# CH32V467RET-R0.net
KiCad netlist of a schematic drawn in Altium Designer
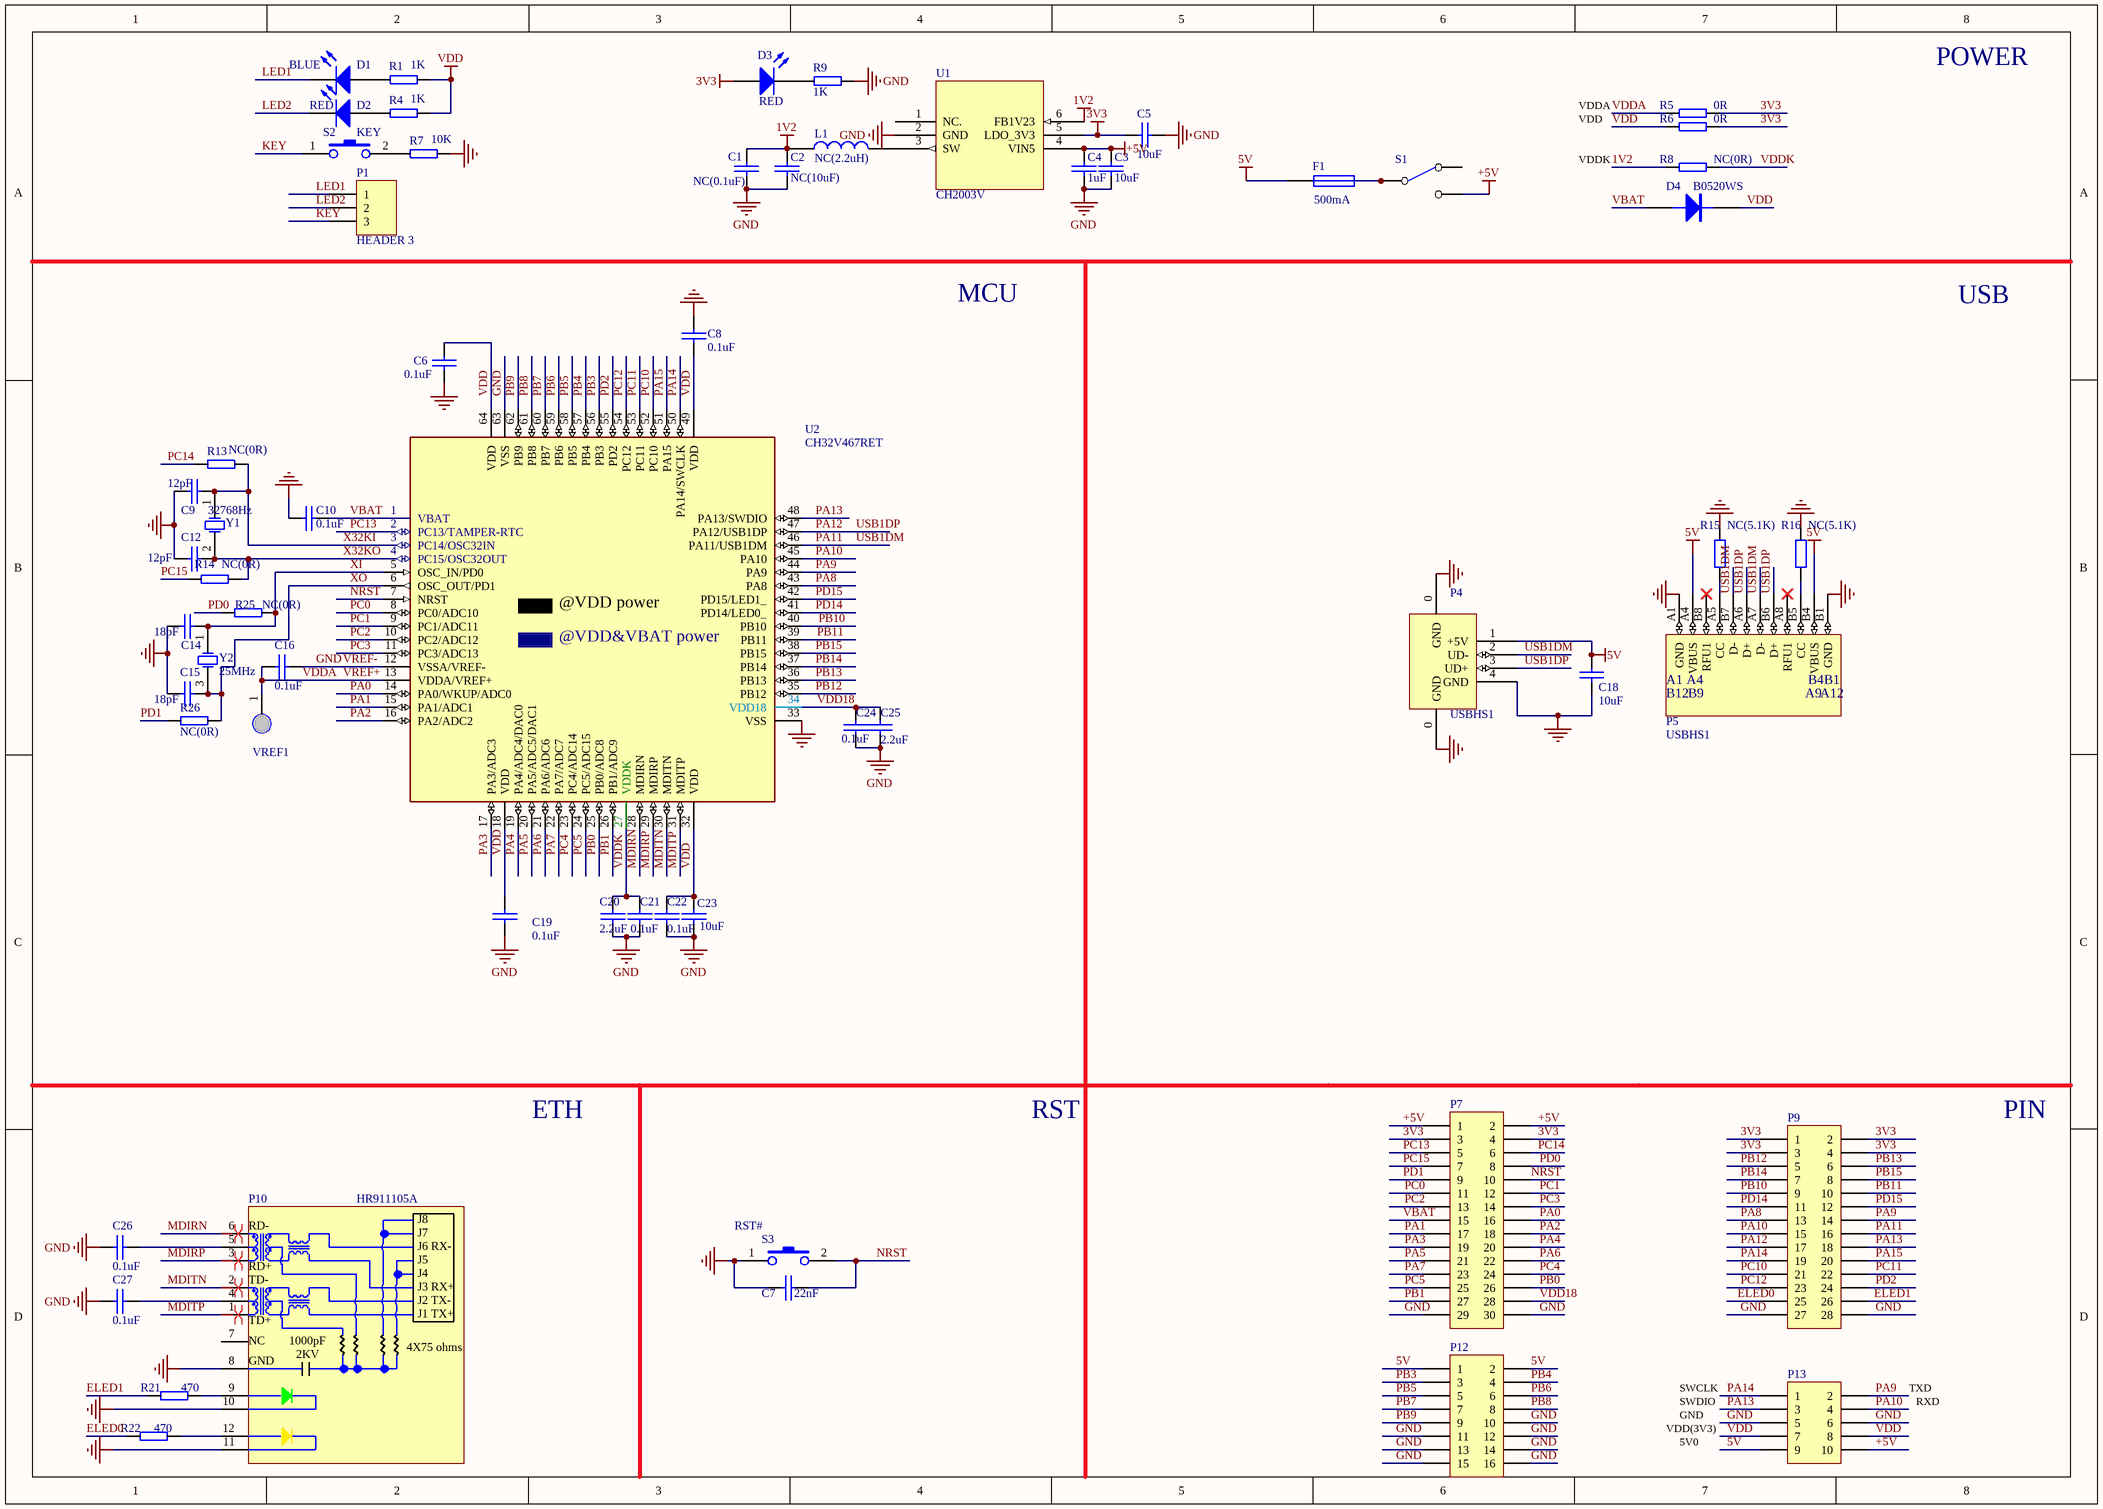
[diagram p0: CH32V467RET-R0.SchDoc]

(export (version "E")
  (design (tool "Eeschema 10.0.6"))
  (components
    (comp (ref "C1")
      (value "NC(0.1uF)")
      (footprint "0402_C")
      (description "Capacitor")
      (libsource (lib "") (part "CAP_2"))
    )
    (comp (ref "C2")
      (value "NC(10uF)")
      (footprint "0603_C")
      (description "Capacitor")
      (libsource (lib "*") (part "CAP"))
    )
    (comp (ref "C3")
      (value "10uF")
      (footprint "0603_C")
      (description "Capacitor")
      (libsource (lib "*") (part "CAP"))
    )
    (comp (ref "C4")
      (value "1uF")
      (footprint "0402_C")
      (description "Capacitor")
      (libsource (lib "") (part "CAP_2"))
    )
    (comp (ref "C5")
      (value "10uF")
      (footprint "0603_C")
      (description "Capacitor")
      (libsource (lib "*") (part "CAP"))
    )
    (comp (ref "C6")
      (value "0.1uF")
      (footprint "0402_C")
      (description "Capacitor")
      (libsource (lib "*") (part "CAP"))
    )
    (comp (ref "C7")
      (value "22nF")
      (footprint "0402_C")
      (description "Capacitor")
      (libsource (lib "") (part "CAP_1"))
    )
    (comp (ref "C8")
      (value "0.1uF")
      (footprint "0402_C")
      (description "Capacitor")
      (libsource (lib "*") (part "CAP"))
    )
    (comp (ref "C9")
      (value "12pF")
      (footprint "0402_C")
      (description "Capacitor")
      (libsource (lib "*") (part "CAP"))
    )
    (comp (ref "C10")
      (value "0.1uF")
      (footprint "0402_C")
      (description "Capacitor")
      (libsource (lib "*") (part "CAP"))
    )
    (comp (ref "C12")
      (value "12pF")
      (footprint "0402_C")
      (description "Capacitor")
      (libsource (lib "*") (part "CAP"))
    )
    (comp (ref "C14")
      (value "18pF")
      (footprint "0402_C")
      (description "Capacitor")
      (libsource (lib "*") (part "CAP"))
    )
    (comp (ref "C15")
      (value "18pF")
      (footprint "0402_C")
      (description "Capacitor")
      (libsource (lib "*") (part "CAP"))
    )
    (comp (ref "C16")
      (value "0.1uF")
      (footprint "0402_C")
      (description "Capacitor")
      (libsource (lib "*") (part "CAP"))
    )
    (comp (ref "C18")
      (value "10uF")
      (footprint "0603_C")
      (description "Capacitor")
      (libsource (lib "") (part "CAP_1"))
    )
    (comp (ref "C19")
      (value "0.1uF")
      (footprint "0402_C")
      (description "Capacitor")
      (libsource (lib "*") (part "CAP"))
    )
    (comp (ref "C20")
      (value "2.2uF")
      (footprint "0402_C")
      (description "Capacitor")
      (libsource (lib "*") (part "CAP"))
    )
    (comp (ref "C21")
      (value "0.1uF")
      (footprint "0402_C")
      (description "Capacitor")
      (libsource (lib "*") (part "CAP"))
    )
    (comp (ref "C22")
      (value "0.1uF")
      (footprint "0402_C")
      (description "Capacitor")
      (libsource (lib "*") (part "CAP"))
    )
    (comp (ref "C23")
      (value "10uF")
      (footprint "0603_C")
      (description "Capacitor")
      (libsource (lib "wch_sch_others") (part "CAP"))
    )
    (comp (ref "C24")
      (value "0.1uF")
      (footprint "0402_C")
      (description "Capacitor")
      (libsource (lib "*") (part "CAP"))
    )
    (comp (ref "C25")
      (value "2.2uF")
      (footprint "0402_C")
      (description "Capacitor")
      (libsource (lib "*") (part "CAP"))
    )
    (comp (ref "C26")
      (value "0.1uF")
      (footprint "0402_C")
      (description "Capacitor")
      (libsource (lib "wch_sch_others") (part "CAP"))
    )
    (comp (ref "C27")
      (value "0.1uF")
      (footprint "0402_C")
      (description "Capacitor")
      (libsource (lib "wch_sch_others") (part "CAP"))
    )
    (comp (ref "D1")
      (value "BLUE")
      (footprint "0603+")
      (description "Typical INFRARED GaAs LED")
      (fields (field (name "PUBLISHER") "Altium Limited"))
      (libsource (lib "*") (part "LED0"))
    )
    (comp (ref "D2")
      (value "RED")
      (footprint "0603+")
      (description "Typical INFRARED GaAs LED")
      (fields (field (name "PUBLISHER") "Altium Limited"))
      (libsource (lib "*") (part "LED0"))
    )
    (comp (ref "D3")
      (value "RED")
      (footprint "0603+")
      (description "Typical INFRARED GaAs LED")
      (fields (field (name "PUBLISHER") "Altium Limited"))
      (libsource (lib "*") (part "LED0"))
    )
    (comp (ref "D4")
      (value "B0520WS")
      (footprint "SOD-323")
      (description "Diode")
      (libsource (lib "*") (part "DIODE"))
    )
    (comp (ref "F1")
      (value "500mA")
      (footprint "0603")
      (description "Fuse")
      (libsource (lib "wch_sch_others") (part "FUSE1"))
    )
    (comp (ref "L1") (value "NC(2.2uH)") (footprint "CD32") (libsource (lib "*") (part "INDUCTOR")))
    (comp (ref "P1")
      (value "HEADER 3")
      (footprint "SIP3-2.54MM")
      (description "Header, 3-Pin")
      (libsource (lib "wch_sch_others") (part "HEADER 3"))
    )
    (comp (ref "P4")
      (value "USBHS1")
      (footprint "USBAF")
      (description "USB Port")
      (libsource (lib "*") (part "USB"))
    )
    (comp (ref "P5")
      (value "USBHS1")
      (footprint "TYPE-C-Receptacle-2.0")
      (libsource (lib "*") (part "TYPE-C1"))
    )
    (comp (ref "P7")
      (value "HEADER 15x2")
      (footprint "MYPCB:IDC30-2.54MM")
      (description "Header, 15-Pin, Dual row")
      (libsource (lib "wch_sch_others") (part "HEADER 15x2"))
    )
    (comp (ref "P9")
      (value "HEADER 14x2")
      (footprint "MYPCB:IDC28-2.54MM")
      (description "Header, 14-Pin, Dual row")
      (libsource (lib "wch_sch_others") (part "HEADER 14x2"))
    )
    (comp (ref "P10") (value "HR911105A") (footprint "HR911105A") (libsource (lib "*") (part "HR911105A")))
    (comp (ref "P12")
      (value "Ppin")
      (footprint "IDC16-2.54mm")
      (description "Header, 8-Pin, Dual row, Right Angle")
      (fields (field (name "PUBLISHER") "Altium Limited"))
      (libsource (lib "Miscellaneous Connectors") (part "Header 8X2H"))
    )
    (comp (ref "P13")
      (value "LINK")
      (footprint "IDC10-2.54mm")
      (description "Header, 5-Pin, Dual row, Right Angle")
      (fields (field (name "PUBLISHER") "Altium Limited"))
      (libsource (lib "Miscellaneous Connectors") (part "Header 5X2H"))
    )
    (comp (ref "R1") (value "1K") (footprint "0402") (libsource (lib "wch_sch_others") (part "RES")))
    (comp (ref "R4") (value "1K") (footprint "0402") (libsource (lib "wch_sch_others") (part "RES")))
    (comp (ref "R5") (value "0R") (footprint "0402") (libsource (lib "*") (part "R")))
    (comp (ref "R6") (value "0R") (footprint "0402") (libsource (lib "*") (part "R")))
    (comp (ref "R7") (value "10K") (footprint "0402") (libsource (lib "wch_sch_others") (part "RES")))
    (comp (ref "R8") (value "NC(0R)") (footprint "0402") (libsource (lib "*") (part "R")))
    (comp (ref "R9") (value "1K") (footprint "0402") (libsource (lib "wch_sch_others") (part "RES")))
    (comp (ref "R13") (value "NC(0R)") (footprint "0402") (libsource (lib "wch_sch_others") (part "RES")))
    (comp (ref "R14") (value "NC(0R)") (footprint "0402") (libsource (lib "wch_sch_others") (part "RES")))
    (comp (ref "R15")
      (value "NC(5.1K)")
      (footprint "0402")
      (description "Resistor")
      (libsource (lib "Miscellaneous Devices") (part "Res2"))
    )
    (comp (ref "R16")
      (value "NC(5.1K)")
      (footprint "0402")
      (description "Resistor")
      (libsource (lib "Miscellaneous Devices") (part "Res2"))
    )
    (comp (ref "R21") (value "470") (footprint "0402") (libsource (lib "wch_sch_others") (part "RES")))
    (comp (ref "R22") (value "470") (footprint "0402") (libsource (lib "wch_sch_others") (part "RES")))
    (comp (ref "R25") (value "NC(0R)") (footprint "0402") (libsource (lib "wch_sch_others") (part "RES")))
    (comp (ref "R26") (value "NC(0R)") (footprint "0402") (libsource (lib "wch_sch_others") (part "RES")))
    (comp (ref "S1") (value "SW SPDT") (footprint "SW1") (libsource (lib "*") (part "SW SPDT")))
    (comp (ref "S2")
      (value "KEY")
      (footprint "SMD_6.1x3.65x2.5mm-KEY")
      (libsource (lib "wch_sch_others") (part "KEY1"))
    )
    (comp (ref "S3")
      (value "RST#")
      (footprint "SMD_6.1x3.65x2.5mm-KEY")
      (libsource (lib "wch_sch_others") (part "KEY1"))
    )
    (comp (ref "U1")
      (value "CH2003V")
      (footprint "SOT-23-6")
      (description "Step-Down DC-DC Converter, 5V input, 1.23V * 800mA output, with LDO 3.3V * 200mA")
      (libsource (lib "CHXXX") (part "CH2003V"))
    )
    (comp (ref "U2")
      (value "CH32V467RET")
      (footprint "LQFP64_7X7")
      (description "RISC-V FPU HD-MCU, 175MHz, USB_480M, 100M Ethernet & Phy, CAN, ADC, DAC, SRAM")
      (libsource (lib "CHXXX") (part "CH32V467RET"))
    )
    (comp (ref "VREF1")
      (value "PAD")
      (footprint "TESTPOINT1")
      (description "焊盘")
      (libsource (lib "wch_sch_others") (part "PAD"))
    )
    (comp (ref "Y1")
      (value "32768Hz")
      (footprint "FC-135")
      (description "Crystal Oscillator")
      (fields (field (name "PUBLISHER") "Altium Limited"))
      (libsource (lib "*") (part "XTAL"))
    )
    (comp (ref "Y2")
      (value "25MHz")
      (footprint "XT3225")
      (description "Crystal Oscillator")
      (fields (field (name "PUBLISHER") "Altium Limited"))
      (libsource (lib "") (part "XTAL_1"))
    )
  )
  (nets
    (net (code "1") (name "+5V") (class "Default")
      (node (ref "C3") (pin "2") (pinfunction "2_2") (pintype "passive"))
      (node (ref "C4") (pin "2") (pinfunction "2_2") (pintype "passive"))
      (node (ref "P13") (pin "10") (pinfunction "10_10") (pintype "passive"))
      (node (ref "P7") (pin "1") (pinfunction "1_1") (pintype "passive"))
      (node (ref "P7") (pin "2") (pinfunction "2_2") (pintype "passive"))
      (node (ref "S1") (pin "2") (pinfunction "NC_2") (pintype "passive"))
      (node (ref "U1") (pin "4") (pinfunction "VIN5_4") (pintype "power_in"))
    )
    (net (code "3") (name "/ELED0") (class "Default")
      (node (ref "P9") (pin "25") (pinfunction "25_25") (pintype "passive"))
      (node (ref "R22") (pin "1") (pintype "passive"))
    )
    (net (code "4") (name "/ELED1") (class "Default")
      (node (ref "P9") (pin "26") (pinfunction "26_26") (pintype "passive"))
      (node (ref "R21") (pin "1") (pintype "passive"))
    )
    (net (code "5") (name "/KEY") (class "Default")
      (node (ref "P1") (pin "3") (pinfunction "3_3") (pintype "passive"))
      (node (ref "S2") (pin "1") (pinfunction "1_1") (pintype "passive"))
    )
    (net (code "6") (name "/LED1") (class "Default")
      (node (ref "D1") (pin "2") (pinfunction "K_2") (pintype "passive"))
      (node (ref "P1") (pin "1") (pinfunction "1_1") (pintype "passive"))
    )
    (net (code "7") (name "/LED2") (class "Default")
      (node (ref "D2") (pin "2") (pinfunction "K_2") (pintype "passive"))
      (node (ref "P1") (pin "2") (pinfunction "2_2") (pintype "passive"))
    )
    (net (code "8") (name "/MDIRN") (class "Default")
      (node (ref "P10") (pin "6") (pintype "passive"))
      (node (ref "U2") (pin "28") (pinfunction "MDIRN_28") (pintype "bidirectional"))
    )
    (net (code "9") (name "/MDIRP") (class "Default")
      (node (ref "P10") (pin "3") (pintype "passive"))
      (node (ref "U2") (pin "29") (pinfunction "MDIRP_29") (pintype "bidirectional"))
    )
    (net (code "10") (name "/MDITN") (class "Default")
      (node (ref "P10") (pin "2") (pintype "passive"))
      (node (ref "U2") (pin "30") (pinfunction "MDITN_30") (pintype "bidirectional"))
    )
    (net (code "11") (name "/MDITP") (class "Default")
      (node (ref "P10") (pin "1") (pintype "passive"))
      (node (ref "U2") (pin "31") (pinfunction "MDITP_31") (pintype "bidirectional"))
    )
    (net (code "12") (name "/NRST") (class "Default")
      (node (ref "C7") (pin "2") (pinfunction "2_2") (pintype "passive"))
      (node (ref "P7") (pin "10") (pinfunction "10_10") (pintype "passive"))
      (node (ref "S3") (pin "2") (pinfunction "2_2") (pintype "passive"))
      (node (ref "U2") (pin "7") (pinfunction "NRST_7") (pintype "input"))
    )
    (net (code "13") (name "/PA0") (class "Default")
      (node (ref "P7") (pin "16") (pinfunction "16_16") (pintype "passive"))
      (node (ref "U2") (pin "14") (pinfunction "PA0/WKUP/ADC0_14") (pintype "bidirectional"))
    )
    (net (code "14") (name "/PA1") (class "Default")
      (node (ref "P7") (pin "17") (pinfunction "17_17") (pintype "passive"))
      (node (ref "U2") (pin "15") (pinfunction "PA1/ADC1_15") (pintype "bidirectional"))
    )
    (net (code "15") (name "/PA2") (class "Default")
      (node (ref "P7") (pin "18") (pinfunction "18_18") (pintype "passive"))
      (node (ref "U2") (pin "16") (pinfunction "PA2/ADC2_16") (pintype "bidirectional"))
    )
    (net (code "16") (name "/PA3") (class "Default")
      (node (ref "P7") (pin "19") (pinfunction "19_19") (pintype "passive"))
      (node (ref "U2") (pin "17") (pinfunction "PA3/ADC3_17") (pintype "bidirectional"))
    )
    (net (code "17") (name "/PA4") (class "Default")
      (node (ref "P7") (pin "20") (pinfunction "20_20") (pintype "passive"))
      (node (ref "U2") (pin "19") (pinfunction "PA4/ADC4/DAC0_19") (pintype "bidirectional"))
    )
    (net (code "18") (name "/PA5") (class "Default")
      (node (ref "P7") (pin "21") (pinfunction "21_21") (pintype "passive"))
      (node (ref "U2") (pin "20") (pinfunction "PA5/ADC5/DAC1_20") (pintype "bidirectional"))
    )
    (net (code "19") (name "/PA6") (class "Default")
      (node (ref "P7") (pin "22") (pinfunction "22_22") (pintype "passive"))
      (node (ref "U2") (pin "21") (pinfunction "PA6/ADC6_21") (pintype "bidirectional"))
    )
    (net (code "20") (name "/PA7") (class "Default")
      (node (ref "P7") (pin "23") (pinfunction "23_23") (pintype "passive"))
      (node (ref "U2") (pin "22") (pinfunction "PA7/ADC7_22") (pintype "bidirectional"))
    )
    (net (code "21") (name "/PA8") (class "Default")
      (node (ref "P9") (pin "13") (pinfunction "13_13") (pintype "passive"))
      (node (ref "U2") (pin "43") (pinfunction "PA8_43") (pintype "bidirectional"))
    )
    (net (code "22") (name "/PA9") (class "Default")
      (node (ref "P13") (pin "2") (pinfunction "2_2") (pintype "passive"))
      (node (ref "P9") (pin "14") (pinfunction "14_14") (pintype "passive"))
      (node (ref "U2") (pin "44") (pinfunction "PA9_44") (pintype "bidirectional"))
    )
    (net (code "23") (name "/PA10") (class "Default")
      (node (ref "P13") (pin "4") (pinfunction "4_4") (pintype "passive"))
      (node (ref "P9") (pin "15") (pinfunction "15_15") (pintype "passive"))
      (node (ref "U2") (pin "45") (pinfunction "PA10_45") (pintype "bidirectional"))
    )
    (net (code "24") (name "/PA11") (class "Default")
      (node (ref "P4") (pin "2") (pinfunction "UD-_2") (pintype "bidirectional"))
      (node (ref "P5") (pin "A7") (pinfunction "D-_A7") (pintype "bidirectional"))
      (node (ref "P5") (pin "B7") (pinfunction "D-_B7") (pintype "bidirectional"))
      (node (ref "P9") (pin "16") (pinfunction "16_16") (pintype "passive"))
      (node (ref "U2") (pin "46") (pinfunction "PA11/USB1DM_46") (pintype "bidirectional"))
    )
    (net (code "25") (name "/PA12") (class "Default")
      (node (ref "P4") (pin "3") (pinfunction "UD+_3") (pintype "bidirectional"))
      (node (ref "P5") (pin "A6") (pinfunction "D+_A6") (pintype "bidirectional"))
      (node (ref "P5") (pin "B6") (pinfunction "D+_B6") (pintype "bidirectional"))
      (node (ref "P9") (pin "17") (pinfunction "17_17") (pintype "passive"))
      (node (ref "U2") (pin "47") (pinfunction "PA12/USB1DP_47") (pintype "bidirectional"))
    )
    (net (code "26") (name "/PA13") (class "Default")
      (node (ref "P13") (pin "3") (pinfunction "3_3") (pintype "passive"))
      (node (ref "P9") (pin "18") (pinfunction "18_18") (pintype "passive"))
      (node (ref "U2") (pin "48") (pinfunction "PA13/SWDIO_48") (pintype "bidirectional"))
    )
    (net (code "27") (name "/PA14") (class "Default")
      (node (ref "P13") (pin "1") (pinfunction "1_1") (pintype "passive"))
      (node (ref "P9") (pin "19") (pinfunction "19_19") (pintype "passive"))
      (node (ref "U2") (pin "50") (pinfunction "PA14/SWCLK_50") (pintype "bidirectional"))
    )
    (net (code "28") (name "/PA15") (class "Default")
      (node (ref "P9") (pin "20") (pinfunction "20_20") (pintype "passive"))
      (node (ref "U2") (pin "51") (pinfunction "PA15_51") (pintype "bidirectional"))
    )
    (net (code "29") (name "/PB0") (class "Default")
      (node (ref "P7") (pin "26") (pinfunction "26_26") (pintype "passive"))
      (node (ref "U2") (pin "25") (pinfunction "PB0/ADC8_25") (pintype "bidirectional"))
    )
    (net (code "30") (name "/PB1") (class "Default")
      (node (ref "P7") (pin "27") (pinfunction "27_27") (pintype "passive"))
      (node (ref "U2") (pin "26") (pinfunction "PB1/ADC9_26") (pintype "bidirectional"))
    )
    (net (code "31") (name "/PB3") (class "Default")
      (node (ref "P12") (pin "3") (pinfunction "3_3") (pintype "passive"))
      (node (ref "U2") (pin "56") (pinfunction "PB3_56") (pintype "bidirectional"))
    )
    (net (code "32") (name "/PB4") (class "Default")
      (node (ref "P12") (pin "4") (pinfunction "4_4") (pintype "passive"))
      (node (ref "U2") (pin "57") (pinfunction "PB4_57") (pintype "bidirectional"))
    )
    (net (code "33") (name "/PB5") (class "Default")
      (node (ref "P12") (pin "5") (pinfunction "5_5") (pintype "passive"))
      (node (ref "U2") (pin "58") (pinfunction "PB5_58") (pintype "bidirectional"))
    )
    (net (code "34") (name "/PB6") (class "Default")
      (node (ref "P12") (pin "6") (pinfunction "6_6") (pintype "passive"))
      (node (ref "U2") (pin "59") (pinfunction "PB6_59") (pintype "bidirectional"))
    )
    (net (code "35") (name "/PB7") (class "Default")
      (node (ref "P12") (pin "7") (pinfunction "7_7") (pintype "passive"))
      (node (ref "U2") (pin "60") (pinfunction "PB7_60") (pintype "bidirectional"))
    )
    (net (code "36") (name "/PB8") (class "Default")
      (node (ref "P12") (pin "8") (pinfunction "8_8") (pintype "passive"))
      (node (ref "U2") (pin "61") (pinfunction "PB8_61") (pintype "bidirectional"))
    )
    (net (code "37") (name "/PB9") (class "Default")
      (node (ref "P12") (pin "9") (pinfunction "9_9") (pintype "passive"))
      (node (ref "U2") (pin "62") (pinfunction "PB9_62") (pintype "bidirectional"))
    )
    (net (code "38") (name "/PB10") (class "Default")
      (node (ref "P9") (pin "9") (pinfunction "9_9") (pintype "passive"))
      (node (ref "U2") (pin "40") (pinfunction "PB10_40") (pintype "bidirectional"))
    )
    (net (code "39") (name "/PB11") (class "Default")
      (node (ref "P9") (pin "10") (pinfunction "10_10") (pintype "passive"))
      (node (ref "U2") (pin "39") (pinfunction "PB11_39") (pintype "bidirectional"))
    )
    (net (code "40") (name "/PB12") (class "Default")
      (node (ref "P9") (pin "5") (pinfunction "5_5") (pintype "passive"))
      (node (ref "U2") (pin "35") (pinfunction "PB12_35") (pintype "bidirectional"))
    )
    (net (code "41") (name "/PB13") (class "Default")
      (node (ref "P9") (pin "6") (pinfunction "6_6") (pintype "passive"))
      (node (ref "U2") (pin "36") (pinfunction "PB13_36") (pintype "bidirectional"))
    )
    (net (code "42") (name "/PB14") (class "Default")
      (node (ref "P9") (pin "7") (pinfunction "7_7") (pintype "passive"))
      (node (ref "U2") (pin "37") (pinfunction "PB14_37") (pintype "bidirectional"))
    )
    (net (code "43") (name "/PB15") (class "Default")
      (node (ref "P9") (pin "8") (pinfunction "8_8") (pintype "passive"))
      (node (ref "U2") (pin "38") (pinfunction "PB15_38") (pintype "bidirectional"))
    )
    (net (code "44") (name "/PC0") (class "Default")
      (node (ref "P7") (pin "11") (pinfunction "11_11") (pintype "passive"))
      (node (ref "U2") (pin "8") (pinfunction "PC0/ADC10_8") (pintype "bidirectional"))
    )
    (net (code "45") (name "/PC1") (class "Default")
      (node (ref "P7") (pin "12") (pinfunction "12_12") (pintype "passive"))
      (node (ref "U2") (pin "9") (pinfunction "PC1/ADC11_9") (pintype "bidirectional"))
    )
    (net (code "46") (name "/PC2") (class "Default")
      (node (ref "P7") (pin "13") (pinfunction "13_13") (pintype "passive"))
      (node (ref "U2") (pin "10") (pinfunction "PC2/ADC12_10") (pintype "bidirectional"))
    )
    (net (code "47") (name "/PC3") (class "Default")
      (node (ref "P7") (pin "14") (pinfunction "14_14") (pintype "passive"))
      (node (ref "U2") (pin "11") (pinfunction "PC3/ADC13_11") (pintype "bidirectional"))
    )
    (net (code "48") (name "/PC4") (class "Default")
      (node (ref "P7") (pin "24") (pinfunction "24_24") (pintype "passive"))
      (node (ref "U2") (pin "23") (pinfunction "PC4/ADC14_23") (pintype "bidirectional"))
    )
    (net (code "49") (name "/PC5") (class "Default")
      (node (ref "P7") (pin "25") (pinfunction "25_25") (pintype "passive"))
      (node (ref "U2") (pin "24") (pinfunction "PC5/ADC15_24") (pintype "bidirectional"))
    )
    (net (code "50") (name "/PC10") (class "Default")
      (node (ref "P9") (pin "21") (pinfunction "21_21") (pintype "passive"))
      (node (ref "U2") (pin "52") (pinfunction "PC10_52") (pintype "bidirectional"))
    )
    (net (code "51") (name "/PC11") (class "Default")
      (node (ref "P9") (pin "22") (pinfunction "22_22") (pintype "passive"))
      (node (ref "U2") (pin "53") (pinfunction "PC11_53") (pintype "bidirectional"))
    )
    (net (code "52") (name "/PC12") (class "Default")
      (node (ref "P9") (pin "23") (pinfunction "23_23") (pintype "passive"))
      (node (ref "U2") (pin "54") (pinfunction "PC12_54") (pintype "bidirectional"))
    )
    (net (code "53") (name "/PC13") (class "Default")
      (node (ref "P7") (pin "5") (pinfunction "5_5") (pintype "passive"))
      (node (ref "U2") (pin "2") (pinfunction "PC13/TAMPER-RTC_2") (pintype "bidirectional"))
    )
    (net (code "54") (name "/PC14") (class "Default")
      (node (ref "P7") (pin "6") (pinfunction "6_6") (pintype "passive"))
      (node (ref "R13") (pin "1") (pintype "passive"))
    )
    (net (code "55") (name "/PC15") (class "Default")
      (node (ref "P7") (pin "7") (pinfunction "7_7") (pintype "passive"))
      (node (ref "R14") (pin "1") (pintype "passive"))
    )
    (net (code "56") (name "/PD0") (class "Default")
      (node (ref "P7") (pin "8") (pinfunction "8_8") (pintype "passive"))
      (node (ref "R25") (pin "1") (pintype "passive"))
    )
    (net (code "57") (name "/PD1") (class "Default")
      (node (ref "P7") (pin "9") (pinfunction "9_9") (pintype "passive"))
      (node (ref "R26") (pin "2") (pintype "passive"))
    )
    (net (code "58") (name "/PD2") (class "Default")
      (node (ref "P9") (pin "24") (pinfunction "24_24") (pintype "passive"))
      (node (ref "U2") (pin "55") (pinfunction "PD2_55") (pintype "bidirectional"))
    )
    (net (code "59") (name "/PD14") (class "Default")
      (node (ref "P9") (pin "11") (pinfunction "11_11") (pintype "passive"))
      (node (ref "U2") (pin "41") (pinfunction "PD14/LED0__41") (pintype "bidirectional"))
    )
    (net (code "60") (name "/PD15") (class "Default")
      (node (ref "P9") (pin "12") (pinfunction "12_12") (pintype "passive"))
      (node (ref "U2") (pin "42") (pinfunction "PD15/LED1__42") (pintype "bidirectional"))
    )
    (net (code "61") (name "/VBAT") (class "Default")
      (node (ref "C10") (pin "2") (pinfunction "2_2") (pintype "passive"))
      (node (ref "D4") (pin "1") (pinfunction "A_1") (pintype "passive"))
      (node (ref "P7") (pin "15") (pinfunction "15_15") (pintype "passive"))
      (node (ref "U2") (pin "1") (pinfunction "VBAT_1") (pintype "power_in"))
    )
    (net (code "62") (name "/VDD18") (class "Default")
      (node (ref "C24") (pin "2") (pinfunction "2_2") (pintype "passive"))
      (node (ref "C25") (pin "2") (pinfunction "2_2") (pintype "passive"))
      (node (ref "P7") (pin "28") (pinfunction "28_28") (pintype "passive"))
      (node (ref "U2") (pin "34") (pinfunction "VDD18_34") (pintype "power_in"))
    )
    (net (code "63") (name "/VDDA") (class "Default")
      (node (ref "C16") (pin "1") (pinfunction "1_1") (pintype "passive"))
      (node (ref "R5") (pin "2") (pinfunction "2_2") (pintype "passive"))
      (node (ref "U2") (pin "13") (pinfunction "VDDA/VREF+_13") (pintype "power_in"))
      (node (ref "VREF1") (pin "1") (pintype "passive"))
    )
    (net (code "64") (name "/VDDK") (class "Default")
      (node (ref "C20") (pin "2") (pinfunction "2_2") (pintype "passive"))
      (node (ref "C21") (pin "2") (pinfunction "2_2") (pintype "passive"))
      (node (ref "R8") (pin "1") (pinfunction "1_1") (pintype "passive"))
      (node (ref "U2") (pin "27") (pinfunction "VDDK_27") (pintype "power_in"))
    )
    (net (code "65") (name "/X32KI") (class "Default")
      (node (ref "C9") (pin "2") (pinfunction "2_2") (pintype "passive"))
      (node (ref "R13") (pin "2") (pintype "passive"))
      (node (ref "U2") (pin "3") (pinfunction "PC14/OSC32IN_3") (pintype "bidirectional"))
      (node (ref "Y1") (pin "1") (pinfunction "OSC1_1") (pintype "passive"))
    )
    (net (code "66") (name "/X32KO") (class "Default")
      (node (ref "C12") (pin "2") (pinfunction "2_2") (pintype "passive"))
      (node (ref "R14") (pin "2") (pintype "passive"))
      (node (ref "U2") (pin "4") (pinfunction "PC15/OSC32OUT_4") (pintype "bidirectional"))
      (node (ref "Y1") (pin "2") (pinfunction "OSC2_2") (pintype "passive"))
    )
    (net (code "67") (name "/XI") (class "Default")
      (node (ref "C14") (pin "2") (pinfunction "2_2") (pintype "passive"))
      (node (ref "R25") (pin "2") (pintype "passive"))
      (node (ref "U2") (pin "5") (pinfunction "OSC_IN/PD0_5") (pintype "input"))
      (node (ref "Y2") (pin "1") (pinfunction "OSC1_1") (pintype "passive"))
    )
    (net (code "68") (name "/XO") (class "Default")
      (node (ref "C15") (pin "2") (pinfunction "2_2") (pintype "passive"))
      (node (ref "R26") (pin "1") (pintype "passive"))
      (node (ref "U2") (pin "6") (pinfunction "OSC_OUT/PD1_6") (pintype "output"))
      (node (ref "Y2") (pin "3") (pinfunction "OSC2_3") (pintype "passive"))
    )
    (net (code "69") (name "1V2") (class "Default")
      (node (ref "C1") (pin "2") (pinfunction "2_2") (pintype "passive"))
      (node (ref "C2") (pin "2") (pinfunction "2_2") (pintype "passive"))
      (node (ref "L1") (pin "2") (pinfunction "2_2") (pintype "passive"))
      (node (ref "R8") (pin "2") (pinfunction "2_2") (pintype "passive"))
      (node (ref "U1") (pin "6") (pinfunction "FB1V23_6") (pintype "input"))
    )
    (net (code "70") (name "3V3") (class "Default")
      (node (ref "C5") (pin "2") (pinfunction "2_2") (pintype "passive"))
      (node (ref "D3") (pin "1") (pinfunction "A_1") (pintype "passive"))
      (node (ref "P7") (pin "3") (pinfunction "3_3") (pintype "passive"))
      (node (ref "P7") (pin "4") (pinfunction "4_4") (pintype "passive"))
      (node (ref "P9") (pin "1") (pinfunction "1_1") (pintype "passive"))
      (node (ref "P9") (pin "2") (pinfunction "2_2") (pintype "passive"))
      (node (ref "P9") (pin "3") (pinfunction "3_3") (pintype "passive"))
      (node (ref "P9") (pin "4") (pinfunction "4_4") (pintype "passive"))
      (node (ref "R5") (pin "1") (pinfunction "1_1") (pintype "passive"))
      (node (ref "R6") (pin "1") (pinfunction "1_1") (pintype "passive"))
      (node (ref "U1") (pin "5") (pinfunction "LDO_3V3_5") (pintype "power_in"))
    )
    (net (code "71") (name "5V") (class "Default")
      (node (ref "C18") (pin "1") (pinfunction "1_1") (pintype "passive"))
      (node (ref "F1") (pin "1") (pinfunction "1_1") (pintype "passive"))
      (node (ref "P12") (pin "1") (pinfunction "1_1") (pintype "passive"))
      (node (ref "P12") (pin "2") (pinfunction "2_2") (pintype "passive"))
      (node (ref "P13") (pin "9") (pinfunction "9_9") (pintype "passive"))
      (node (ref "P4") (pin "1") (pinfunction "+5V_1") (pintype "power_in"))
      (node (ref "P5") (pin "A4") (pinfunction "VBUS_A4") (pintype "bidirectional"))
      (node (ref "P5") (pin "B4") (pinfunction "VBUS_B4") (pintype "bidirectional"))
    )
    (net (code "72") (name "GND") (class "Default")
      (node (ref "C1") (pin "1") (pinfunction "1_1") (pintype "passive"))
      (node (ref "C10") (pin "1") (pinfunction "1_1") (pintype "passive"))
      (node (ref "C12") (pin "1") (pinfunction "1_1") (pintype "passive"))
      (node (ref "C14") (pin "1") (pinfunction "1_1") (pintype "passive"))
      (node (ref "C15") (pin "1") (pinfunction "1_1") (pintype "passive"))
      (node (ref "C16") (pin "2") (pinfunction "2_2") (pintype "passive"))
      (node (ref "C18") (pin "2") (pinfunction "2_2") (pintype "passive"))
      (node (ref "C19") (pin "1") (pinfunction "1_1") (pintype "passive"))
      (node (ref "C2") (pin "1") (pinfunction "1_1") (pintype "passive"))
      (node (ref "C20") (pin "1") (pinfunction "1_1") (pintype "passive"))
      (node (ref "C21") (pin "1") (pinfunction "1_1") (pintype "passive"))
      (node (ref "C22") (pin "1") (pinfunction "1_1") (pintype "passive"))
      (node (ref "C23") (pin "1") (pinfunction "1_1") (pintype "passive"))
      (node (ref "C24") (pin "1") (pinfunction "1_1") (pintype "passive"))
      (node (ref "C25") (pin "1") (pinfunction "1_1") (pintype "passive"))
      (node (ref "C26") (pin "1") (pinfunction "1_1") (pintype "passive"))
      (node (ref "C27") (pin "1") (pinfunction "1_1") (pintype "passive"))
      (node (ref "C3") (pin "1") (pinfunction "1_1") (pintype "passive"))
      (node (ref "C4") (pin "1") (pinfunction "1_1") (pintype "passive"))
      (node (ref "C5") (pin "1") (pinfunction "1_1") (pintype "passive"))
      (node (ref "C6") (pin "1") (pinfunction "1_1") (pintype "passive"))
      (node (ref "C7") (pin "1") (pinfunction "1_1") (pintype "passive"))
      (node (ref "C8") (pin "2") (pinfunction "2_2") (pintype "passive"))
      (node (ref "C9") (pin "1") (pinfunction "1_1") (pintype "passive"))
      (node (ref "P10") (pin "10") (pintype "passive"))
      (node (ref "P10") (pin "11") (pintype "passive"))
      (node (ref "P10") (pin "8") (pintype "passive"))
      (node (ref "P12") (pin "10") (pinfunction "10_10") (pintype "passive"))
      (node (ref "P12") (pin "11") (pinfunction "11_11") (pintype "passive"))
      (node (ref "P12") (pin "12") (pinfunction "12_12") (pintype "passive"))
      (node (ref "P12") (pin "13") (pinfunction "13_13") (pintype "passive"))
      (node (ref "P12") (pin "14") (pinfunction "14_14") (pintype "passive"))
      (node (ref "P12") (pin "15") (pinfunction "15_15") (pintype "passive"))
      (node (ref "P12") (pin "16") (pinfunction "16_16") (pintype "passive"))
      (node (ref "P13") (pin "5") (pinfunction "5_5") (pintype "passive"))
      (node (ref "P13") (pin "6") (pinfunction "6_6") (pintype "passive"))
      (node (ref "P4") (pin "0") (pinfunction "GND_0") (pintype "power_in"))
      (node (ref "P4") (pin "4") (pinfunction "GND_4") (pintype "power_in"))
      (node (ref "P5") (pin "A1") (pinfunction "GND_A1") (pintype "bidirectional"))
      (node (ref "P5") (pin "B1") (pinfunction "GND_B1") (pintype "bidirectional"))
      (node (ref "P7") (pin "29") (pinfunction "29_29") (pintype "passive"))
      (node (ref "P7") (pin "30") (pinfunction "30_30") (pintype "passive"))
      (node (ref "P9") (pin "27") (pinfunction "27_27") (pintype "passive"))
      (node (ref "P9") (pin "28") (pinfunction "28_28") (pintype "passive"))
      (node (ref "R15") (pin "2") (pinfunction "2_2") (pintype "passive"))
      (node (ref "R16") (pin "2") (pinfunction "2_2") (pintype "passive"))
      (node (ref "R7") (pin "1") (pintype "passive"))
      (node (ref "R9") (pin "2") (pintype "passive"))
      (node (ref "S3") (pin "1") (pinfunction "1_1") (pintype "passive"))
      (node (ref "U1") (pin "2") (pinfunction "GND_2") (pintype "power_in"))
      (node (ref "U2") (pin "12") (pinfunction "VSSA/VREF-_12") (pintype "power_in"))
      (node (ref "U2") (pin "33") (pinfunction "VSS_33") (pintype "power_in"))
      (node (ref "U2") (pin "63") (pinfunction "VSS_63") (pintype "power_in"))
    )
    (net (code "73") (name "Net-(C26-Pad2)") (class "Default")
      (node (ref "C26") (pin "2") (pinfunction "2_2") (pintype "passive"))
      (node (ref "P10") (pin "5") (pintype "passive"))
    )
    (net (code "74") (name "Net-(C27-Pad2)") (class "Default")
      (node (ref "C27") (pin "2") (pinfunction "2_2") (pintype "passive"))
      (node (ref "P10") (pin "4") (pintype "passive"))
    )
    (net (code "75") (name "Net-(D1-A)") (class "Default")
      (node (ref "D1") (pin "1") (pinfunction "A_1") (pintype "passive"))
      (node (ref "R1") (pin "2") (pintype "passive"))
    )
    (net (code "76") (name "Net-(D2-A)") (class "Default")
      (node (ref "D2") (pin "1") (pinfunction "A_1") (pintype "passive"))
      (node (ref "R4") (pin "2") (pintype "passive"))
    )
    (net (code "77") (name "Net-(D3-K)") (class "Default")
      (node (ref "D3") (pin "2") (pinfunction "K_2") (pintype "passive"))
      (node (ref "R9") (pin "1") (pintype "passive"))
    )
    (net (code "78") (name "Net-(P5-CC-PadA5)") (class "Default")
      (node (ref "P5") (pin "A5") (pinfunction "CC_A5") (pintype "bidirectional"))
      (node (ref "R15") (pin "1") (pinfunction "1_1") (pintype "passive"))
    )
    (net (code "79") (name "Net-(P5-CC-PadB5)") (class "Default")
      (node (ref "P5") (pin "B5") (pinfunction "CC_B5") (pintype "bidirectional"))
      (node (ref "R16") (pin "1") (pinfunction "1_1") (pintype "passive"))
    )
    (net (code "80") (name "Net-(P10-Pad9)") (class "Default")
      (node (ref "P10") (pin "9") (pintype "passive"))
      (node (ref "R21") (pin "2") (pintype "passive"))
    )
    (net (code "81") (name "Net-(P10-Pad12)") (class "Default")
      (node (ref "P10") (pin "12") (pintype "passive"))
      (node (ref "R22") (pin "2") (pintype "passive"))
    )
    (net (code "82") (name "Net-(R7-Pad2)") (class "Default")
      (node (ref "R7") (pin "2") (pintype "passive"))
      (node (ref "S2") (pin "2") (pinfunction "2_2") (pintype "passive"))
    )
    (net (code "83") (name "Net-(S1-COMMON)") (class "Default")
      (node (ref "F1") (pin "2") (pinfunction "2_2") (pintype "passive"))
      (node (ref "S1") (pin "1") (pinfunction "COMMON_1") (pintype "passive"))
    )
    (net (code "84") (name "Net-(U1-SW)") (class "Default")
      (node (ref "L1") (pin "1") (pinfunction "1_1") (pintype "passive"))
      (node (ref "U1") (pin "3") (pinfunction "SW_3") (pintype "output"))
    )
    (net (code "85") (name "VDD") (class "Default")
      (node (ref "C19") (pin "2") (pinfunction "2_2") (pintype "passive"))
      (node (ref "C22") (pin "2") (pinfunction "2_2") (pintype "passive"))
      (node (ref "C23") (pin "2") (pinfunction "2_2") (pintype "passive"))
      (node (ref "C6") (pin "2") (pinfunction "2_2") (pintype "passive"))
      (node (ref "C8") (pin "1") (pinfunction "1_1") (pintype "passive"))
      (node (ref "D4") (pin "2") (pinfunction "K_2") (pintype "passive"))
      (node (ref "P13") (pin "7") (pinfunction "7_7") (pintype "passive"))
      (node (ref "P13") (pin "8") (pinfunction "8_8") (pintype "passive"))
      (node (ref "R1") (pin "1") (pintype "passive"))
      (node (ref "R4") (pin "1") (pintype "passive"))
      (node (ref "R6") (pin "2") (pinfunction "2_2") (pintype "passive"))
      (node (ref "U2") (pin "18") (pinfunction "VDD_18") (pintype "power_in"))
      (node (ref "U2") (pin "32") (pinfunction "VDD_32") (pintype "power_in"))
      (node (ref "U2") (pin "49") (pinfunction "VDD_49") (pintype "power_in"))
      (node (ref "U2") (pin "64") (pinfunction "VDD_64") (pintype "power_in"))
    )
    (net (code "86") (name "unconnected-(P5-RFU1-PadA8)") (class "Default")
      (node (ref "P5") (pin "A8") (pinfunction "RFU1_A8") (pintype "bidirectional+no_connect"))
    )
    (net (code "87") (name "unconnected-(P5-RFU1-PadB8)") (class "Default")
      (node (ref "P5") (pin "B8") (pinfunction "RFU1_B8") (pintype "bidirectional+no_connect"))
    )
    (net (code "88") (name "unconnected-(P10-Pad7)") (class "Default")
      (node (ref "P10") (pin "7") (pintype "passive"))
    )
    (net (code "89") (name "unconnected-(S1-NO-Pad3)") (class "Default")
      (node (ref "S1") (pin "3") (pinfunction "NO_3") (pintype "passive"))
    )
    (net (code "90") (name "unconnected-(U1-NC.-Pad1)") (class "Default")
      (node (ref "U1") (pin "1") (pinfunction "NC._1") (pintype "passive"))
    )
  )
)
